# parakeet_board_rev_1_0.net
KiCad netlist of a schematic drawn in EAGLE
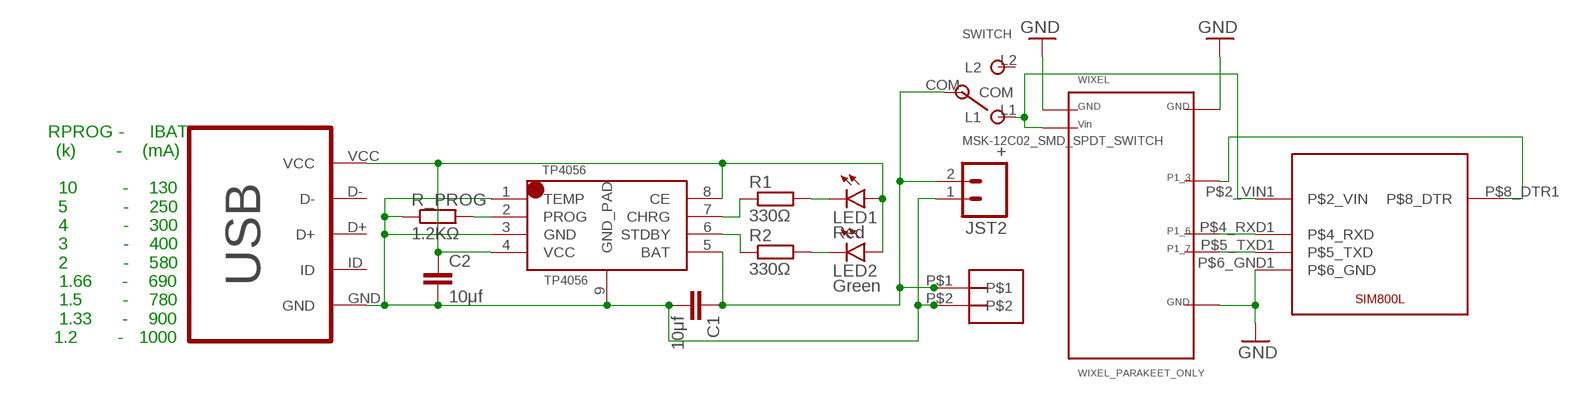
[diagram p0: schematic, sheet 1]

(export (version "E")
  (design (tool "Eeschema 10.0.6"))
  (components
    (comp (ref "C1")
      (value "10μf")
      (footprint "eagle-import:C1206")
      (libsource (lib "eagle-import") (part "C-EUC1206"))
    )
    (comp (ref "C2")
      (value "10μf")
      (footprint "eagle-import:C1206")
      (libsource (lib "eagle-import") (part "C-EUC1206"))
    )
    (comp (ref "JST-XH")
      (value "2_PIN_JST-XH-B2B")
      (footprint "eagle-import:2_PIN_JST-XH-B2B")
      (libsource (lib "eagle-import") (part "2_PIN_JST-XH-B2B"))
    )
    (comp (ref "JST2")
      (value "+")
      (footprint "eagle-import:JST-2-SMD")
      (libsource (lib "eagle-import") (part "M02-JST-2MM-SMT"))
    )
    (comp (ref "LED1")
      (value "Red")
      (footprint "eagle-import:LED-1206")
      (libsource (lib "eagle-import") (part "LED1206"))
    )
    (comp (ref "LED2")
      (value "Green")
      (footprint "eagle-import:LED-1206")
      (libsource (lib "eagle-import") (part "LED1206"))
    )
    (comp (ref "R1")
      (value "330Ω")
      (footprint "eagle-import:R1206")
      (libsource (lib "eagle-import") (part "R-EU_R1206"))
    )
    (comp (ref "R2")
      (value "330Ω")
      (footprint "eagle-import:R1206")
      (libsource (lib "eagle-import") (part "R-EU_R1206"))
    )
    (comp (ref "R_PROG")
      (value "1.2KΩ")
      (footprint "eagle-import:R1206")
      (libsource (lib "eagle-import") (part "R-EU_R1206"))
    )
    (comp (ref "SIM800L")
      (value "SIM800L_PARAKEET_ONLY")
      (footprint "eagle-import:SIM800L_PARAKEET_ONLY")
      (libsource (lib "eagle-import") (part "SIM800L_PARAKEET_ONLY"))
    )
    (comp (ref "SWITCH")
      (value "MSK-12C02_SMD_SPDT_SWITCH")
      (footprint "eagle-import:MSK-12C02")
      (libsource (lib "eagle-import") (part "MSK-12C02_SMD_SPDT_SWITCH"))
    )
    (comp (ref "TP4056")
      (value "TP4056")
      (footprint "eagle-import:SOP-8")
      (libsource (lib "eagle-import") (part "TP4056"))
    )
    (comp (ref "USB")
      (value "MICRO-USB-B")
      (footprint "eagle-import:MICRO_USB_4_LEGS")
      (libsource (lib "eagle-import") (part "MICRO-USB-B"))
    )
    (comp (ref "WIXEL")
      (value "WIXEL_PARAKEET_ONLY")
      (footprint "eagle-import:WIXEL_PARAKEET_ONLY")
      (libsource (lib "eagle-import") (part "WIXEL_PARAKEET_ONLY"))
    )
  )
  (nets
    (net (code "1") (name "GND") (class "Default")
      (node (ref "C1") (pin "2") (pinfunction "2_2") (pintype "passive"))
      (node (ref "C2") (pin "2") (pinfunction "2_2") (pintype "passive"))
      (node (ref "JST-XH") (pin "P$2") (pinfunction "P$2_P$2") (pintype "bidirectional"))
      (node (ref "JST2") (pin "1") (pinfunction "2_1") (pintype "passive"))
      (node (ref "R_PROG") (pin "1") (pinfunction "1_1") (pintype "passive"))
      (node (ref "SIM800L") (pin "P$6_GND1") (pinfunction "P$6_GND_P$6_GND1") (pintype "bidirectional"))
      (node (ref "TP4056") (pin "1") (pinfunction "TEMP_1") (pintype "bidirectional"))
      (node (ref "TP4056") (pin "3") (pinfunction "GND_3") (pintype "bidirectional"))
      (node (ref "TP4056") (pin "9") (pinfunction "GND_PAD_9") (pintype "bidirectional"))
      (node (ref "USB") (pin "GND") (pinfunction "GND_GND") (pintype "bidirectional"))
      (node (ref "WIXEL") (pin "P$1") (pinfunction "P$1-GND1_P$1") (pintype "bidirectional"))
      (node (ref "WIXEL") (pin "P$12") (pinfunction "P$12-GND2_P$12") (pintype "bidirectional"))
      (node (ref "WIXEL") (pin "P$23") (pinfunction "P$23-GND3_P$23") (pintype "bidirectional"))
    )
    (net (code "2") (name "Net-(JST2-1)") (class "Default")
      (node (ref "C1") (pin "1") (pinfunction "1_1") (pintype "passive"))
      (node (ref "JST-XH") (pin "P$1") (pinfunction "P$1_P$1") (pintype "bidirectional"))
      (node (ref "JST2") (pin "2") (pinfunction "1_2") (pintype "passive"))
      (node (ref "SWITCH") (pin "COM") (pinfunction "COM_COM") (pintype "bidirectional"))
      (node (ref "TP4056") (pin "5") (pinfunction "BAT_5") (pintype "bidirectional"))
    )
    (net (code "3") (name "Net-(LED1-PadC)") (class "Default")
      (node (ref "LED1") (pin "C") (pinfunction "C_C") (pintype "passive"))
      (node (ref "R1") (pin "2") (pinfunction "2_2") (pintype "passive"))
    )
    (net (code "4") (name "Net-(LED2-PadC)") (class "Default")
      (node (ref "LED2") (pin "C") (pinfunction "C_C") (pintype "passive"))
      (node (ref "R2") (pin "2") (pinfunction "2_2") (pintype "passive"))
    )
    (net (code "5") (name "Net-(SIM800L-P$2_VIN)") (class "Default")
      (node (ref "SIM800L") (pin "P$2_VIN1") (pinfunction "P$2_VIN_P$2_VIN1") (pintype "bidirectional"))
      (node (ref "SWITCH") (pin "L1") (pinfunction "L1_L1") (pintype "bidirectional"))
      (node (ref "WIXEL") (pin "P$2") (pinfunction "P$2-VIN_P$2") (pintype "bidirectional"))
    )
    (net (code "6") (name "Net-(SIM800L-P$4_RXD)") (class "Default")
      (node (ref "SIM800L") (pin "P$4_RXD1") (pinfunction "P$4_RXD_P$4_RXD1") (pintype "bidirectional"))
      (node (ref "WIXEL") (pin "P$19") (pinfunction "P$19-P1_6_P$19") (pintype "bidirectional"))
    )
    (net (code "7") (name "Net-(SIM800L-P$5_TXD)") (class "Default")
      (node (ref "SIM800L") (pin "P$5_TXD1") (pinfunction "P$5_TXD_P$5_TXD1") (pintype "bidirectional"))
      (node (ref "WIXEL") (pin "P$20") (pinfunction "P$20-P1_7_P$20") (pintype "bidirectional"))
    )
    (net (code "8") (name "Net-(SIM800L-P$8_DTR)") (class "Default")
      (node (ref "SIM800L") (pin "P$8_DTR1") (pinfunction "P$8_DTR_P$8_DTR1") (pintype "bidirectional"))
      (node (ref "WIXEL") (pin "P$16") (pinfunction "P$16-P1_3_P$16") (pintype "bidirectional"))
    )
    (net (code "9") (name "Net-(TP4056-CE)") (class "Default")
      (node (ref "C2") (pin "1") (pinfunction "1_1") (pintype "passive"))
      (node (ref "LED1") (pin "A") (pinfunction "A_A") (pintype "passive"))
      (node (ref "LED2") (pin "A") (pinfunction "A_A") (pintype "passive"))
      (node (ref "TP4056") (pin "4") (pinfunction "VCC_4") (pintype "bidirectional"))
      (node (ref "TP4056") (pin "8") (pinfunction "CE_8") (pintype "bidirectional"))
      (node (ref "USB") (pin "VCC") (pinfunction "VCC_VCC") (pintype "bidirectional"))
    )
    (net (code "10") (name "Net-(TP4056-CHRG)") (class "Default")
      (node (ref "R1") (pin "1") (pinfunction "1_1") (pintype "passive"))
      (node (ref "TP4056") (pin "7") (pinfunction "CHRG_7") (pintype "bidirectional"))
    )
    (net (code "11") (name "Net-(TP4056-PROG)") (class "Default")
      (node (ref "R_PROG") (pin "2") (pinfunction "2_2") (pintype "passive"))
      (node (ref "TP4056") (pin "2") (pinfunction "PROG_2") (pintype "bidirectional"))
    )
    (net (code "12") (name "Net-(TP4056-STDBY)") (class "Default")
      (node (ref "R2") (pin "1") (pinfunction "1_1") (pintype "passive"))
      (node (ref "TP4056") (pin "6") (pinfunction "STDBY_6") (pintype "bidirectional"))
    )
    (net (code "13") (name "unconnected-(SWITCH-PadL2)") (class "Default")
      (node (ref "SWITCH") (pin "L2") (pinfunction "L2_L2") (pintype "bidirectional"))
    )
    (net (code "14") (name "unconnected-(USB-PadD+)") (class "Default")
      (node (ref "USB") (pin "D+") (pinfunction "D+_D+") (pintype "bidirectional"))
    )
    (net (code "15") (name "unconnected-(USB-PadD-)") (class "Default")
      (node (ref "USB") (pin "D-") (pinfunction "D-_D-") (pintype "bidirectional"))
    )
    (net (code "16") (name "unconnected-(USB-PadID)") (class "Default")
      (node (ref "USB") (pin "ID") (pinfunction "ID_ID") (pintype "bidirectional"))
    )
  )
)
